# ppg_array_wireless.net
KiCad netlist of a schematic drawn in EAGLE
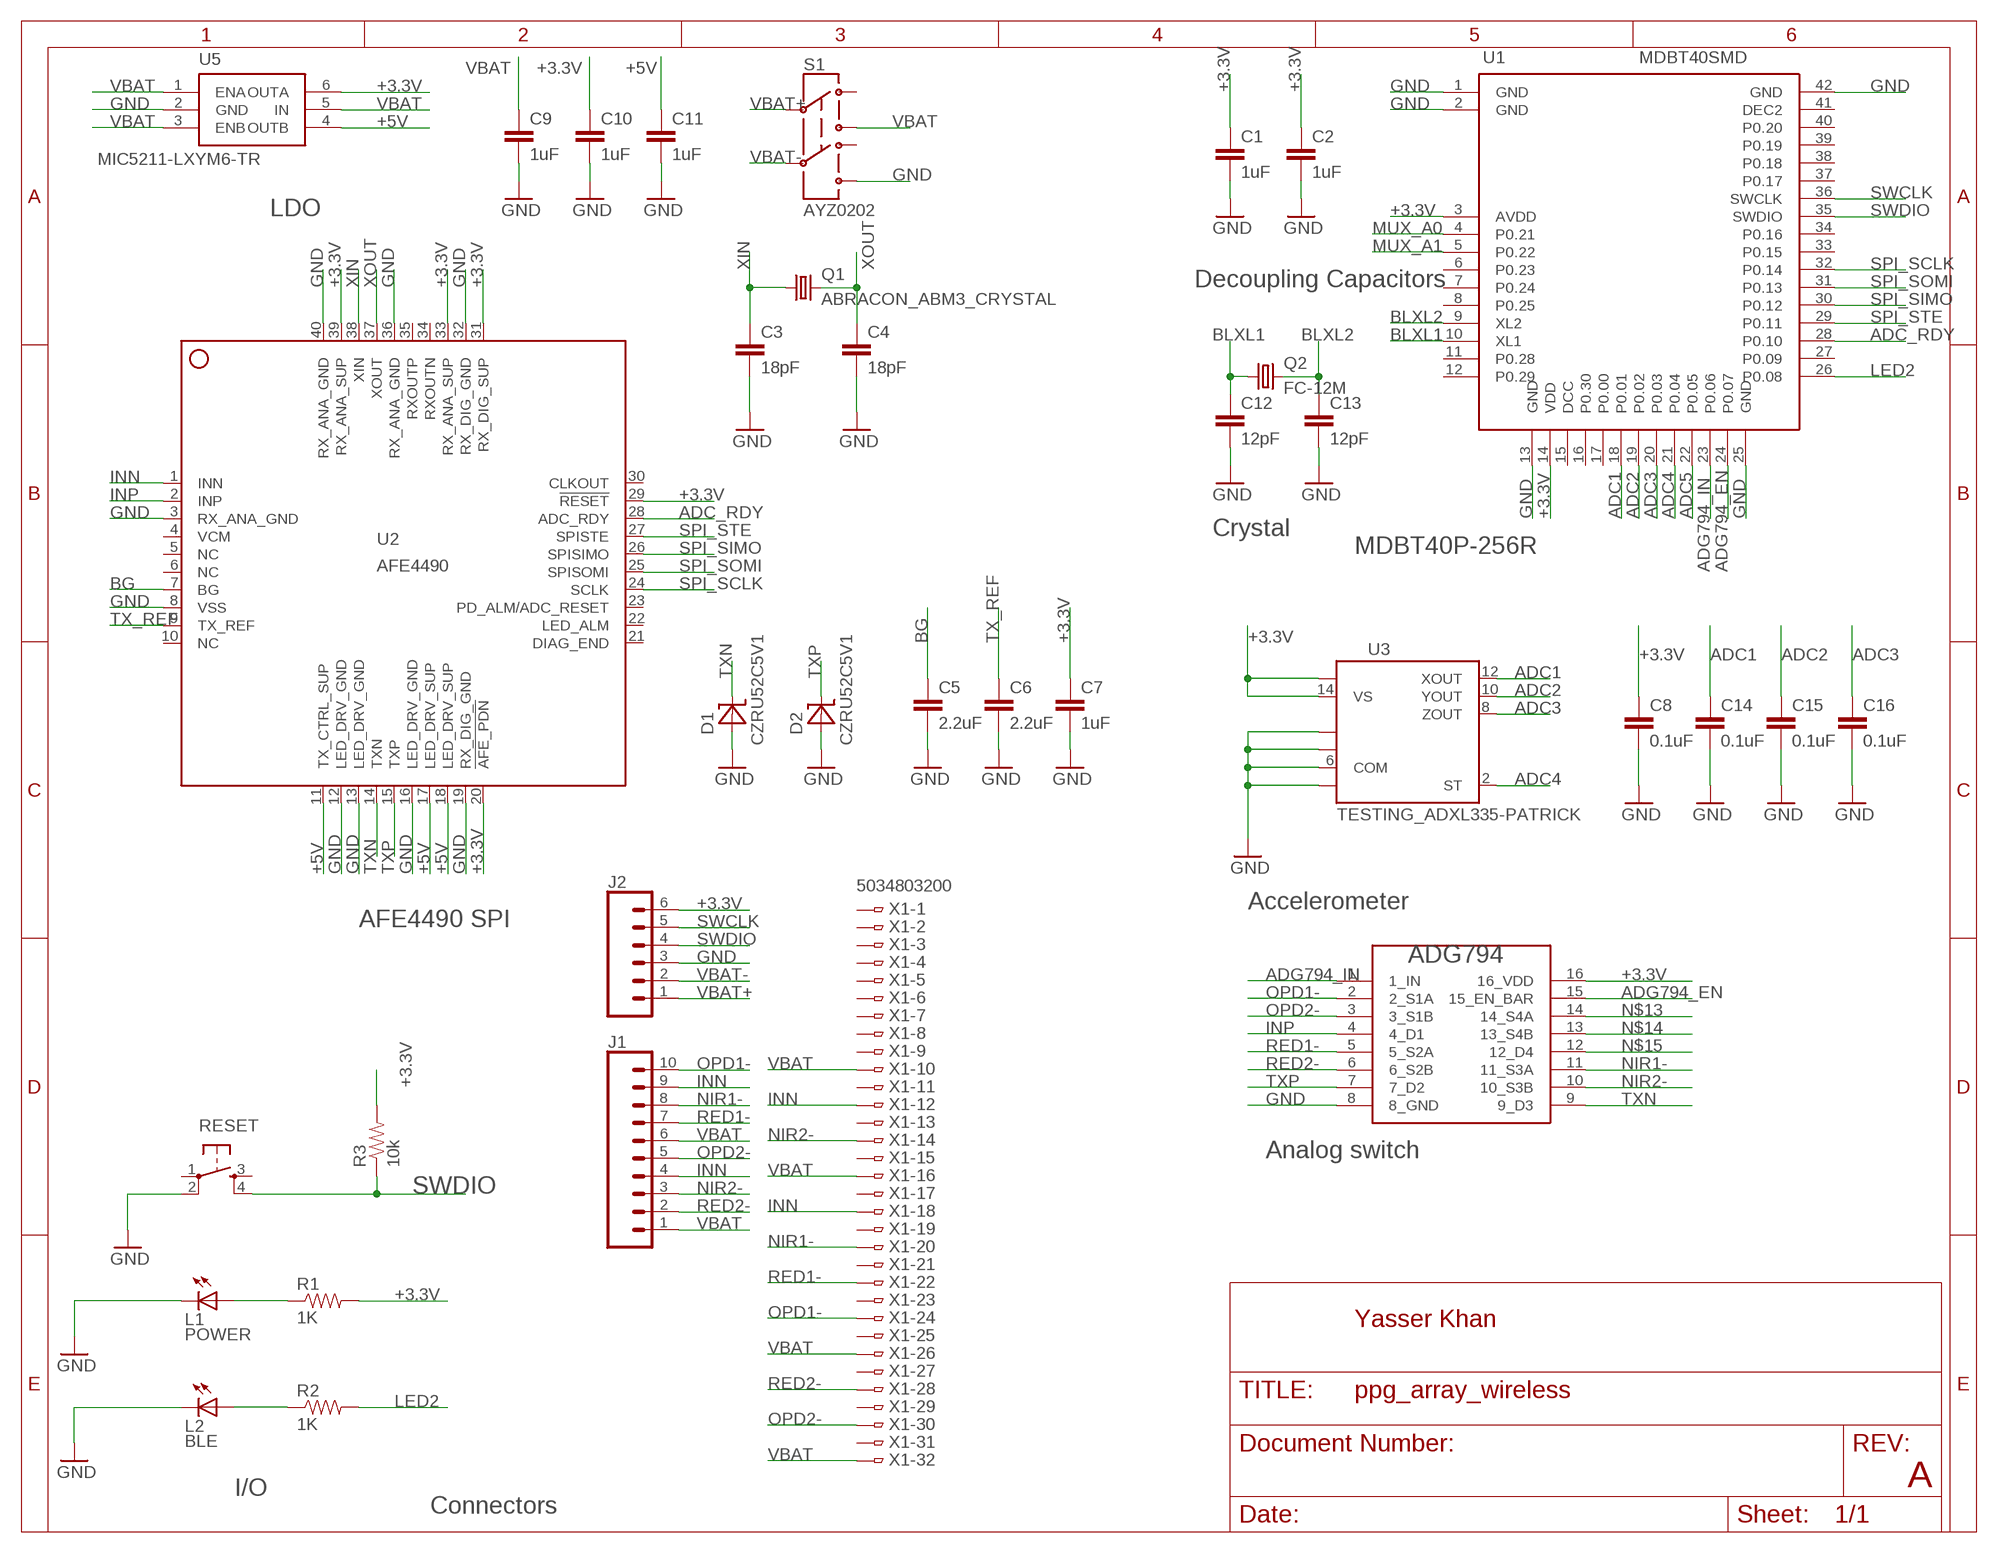
[diagram p0: schematic, sheet 1]

(export (version "E")
  (design (tool "Eeschema 10.0.6"))
  (components
    (comp (ref "C1")
      (value "1uF")
      (footprint "eagle-import:0603-CAP")
      (libsource (lib "eagle-import") (part "CAP0603-CAP"))
    )
    (comp (ref "C2")
      (value "1uF")
      (footprint "eagle-import:0603-CAP")
      (libsource (lib "eagle-import") (part "CAP0603-CAP"))
    )
    (comp (ref "C3")
      (value "18pF")
      (footprint "eagle-import:0603-CAP")
      (libsource (lib "eagle-import") (part "CAP0603-CAP"))
    )
    (comp (ref "C4")
      (value "18pF")
      (footprint "eagle-import:0603-CAP")
      (libsource (lib "eagle-import") (part "CAP0603-CAP"))
    )
    (comp (ref "C5")
      (value "2.2uF")
      (footprint "eagle-import:0603-CAP")
      (libsource (lib "eagle-import") (part "CAP0603-CAP"))
    )
    (comp (ref "C6")
      (value "2.2uF")
      (footprint "eagle-import:0603-CAP")
      (libsource (lib "eagle-import") (part "CAP0603-CAP"))
    )
    (comp (ref "C7")
      (value "1uF")
      (footprint "eagle-import:0603-CAP")
      (libsource (lib "eagle-import") (part "CAP0603-CAP"))
    )
    (comp (ref "C8")
      (value "0.1uF")
      (footprint "eagle-import:0603-CAP")
      (libsource (lib "eagle-import") (part "CAP0603-CAP"))
    )
    (comp (ref "C9")
      (value "1uF")
      (footprint "eagle-import:0603-CAP")
      (libsource (lib "eagle-import") (part "CAP0603-CAP"))
    )
    (comp (ref "C10")
      (value "1uF")
      (footprint "eagle-import:0603-CAP")
      (libsource (lib "eagle-import") (part "CAP0603-CAP"))
    )
    (comp (ref "C11")
      (value "1uF")
      (footprint "eagle-import:0603-CAP")
      (libsource (lib "eagle-import") (part "CAP0603-CAP"))
    )
    (comp (ref "C12")
      (value "12pF")
      (footprint "eagle-import:0603-CAP")
      (libsource (lib "eagle-import") (part "CAP0603-CAP"))
    )
    (comp (ref "C13")
      (value "12pF")
      (footprint "eagle-import:0603-CAP")
      (libsource (lib "eagle-import") (part "CAP0603-CAP"))
    )
    (comp (ref "C14")
      (value "0.1uF")
      (footprint "eagle-import:0603-CAP")
      (libsource (lib "eagle-import") (part "CAP0603-CAP"))
    )
    (comp (ref "C15")
      (value "0.1uF")
      (footprint "eagle-import:0603-CAP")
      (libsource (lib "eagle-import") (part "CAP0603-CAP"))
    )
    (comp (ref "C16")
      (value "0.1uF")
      (footprint "eagle-import:0603-CAP")
      (libsource (lib "eagle-import") (part "CAP0603-CAP"))
    )
    (comp (ref "D1")
      (value "CZRU52C5V1")
      (footprint "eagle-import:CZRU52C5V1")
      (libsource (lib "eagle-import") (part "CZRU52C5V1"))
    )
    (comp (ref "D2")
      (value "CZRU52C5V1")
      (footprint "eagle-import:CZRU52C5V1")
      (libsource (lib "eagle-import") (part "CZRU52C5V1"))
    )
    (comp (ref "J1")
      (value "CONN_10\"")
      (footprint "eagle-import:1X10")
      (libsource (lib "eagle-import") (part "CONN_10{dblquote}"))
    )
    (comp (ref "J2")
      (value "CONN_06SILK_FEMALE_PTH")
      (footprint "eagle-import:1X06")
      (libsource (lib "eagle-import") (part "CONN_06SILK_FEMALE_PTH"))
    )
    (comp (ref "L1")
      (value "POWER")
      (footprint "eagle-import:CHIP-LED0603")
      (libsource (lib "eagle-import") (part "LEDCHIP-LED0603"))
    )
    (comp (ref "L2")
      (value "BLE")
      (footprint "eagle-import:CHIP-LED0603")
      (libsource (lib "eagle-import") (part "LEDCHIP-LED0603"))
    )
    (comp (ref "Q1")
      (value "ABRACON_ABM3_CRYSTAL")
      (footprint "eagle-import:ABRACON_ABM3_CRYSTAL")
      (libsource (lib "eagle-import") (part "ABRACON_ABM3_CRYSTAL"))
    )
    (comp (ref "Q2")
      (value "FC-12M")
      (footprint "eagle-import:FC-12M")
      (libsource (lib "eagle-import") (part "FC-12M"))
    )
    (comp (ref "R1")
      (value "1K")
      (footprint "eagle-import:0603-RES")
      (libsource (lib "eagle-import") (part "RESISTOR0603-RES"))
    )
    (comp (ref "R2")
      (value "1K")
      (footprint "eagle-import:0603-RES")
      (libsource (lib "eagle-import") (part "RESISTOR0603-RES"))
    )
    (comp (ref "R3")
      (value "10k")
      (footprint "eagle-import:0603-RES")
      (libsource (lib "eagle-import") (part "RESISTOR0603-RES"))
    )
    (comp (ref "RESET")
      (value "TAC_SWITCHSMD")
      (footprint "eagle-import:TACTILE_SWITCH_SMD")
      (libsource (lib "eagle-import") (part "TAC_SWITCHSMD"))
    )
    (comp (ref "S1")
      (value "AYZ0202")
      (footprint "eagle-import:AYZ0202")
      (libsource (lib "eagle-import") (part "AYZ0202"))
    )
    (comp (ref "U1")
      (value "MDBT40SMD")
      (footprint "eagle-import:MDBT40")
      (libsource (lib "eagle-import") (part "MDBT40SMD"))
    )
    (comp (ref "U2")
      (value "AFE4490")
      (footprint "eagle-import:QFN40-6X6")
      (libsource (lib "eagle-import") (part "AFE4490"))
    )
    (comp (ref "U3")
      (value "TESTING_ADXL335-PATRICK")
      (footprint "eagle-import:TESTING_LFCSP-16")
      (libsource (lib "eagle-import") (part "TESTING_ADXL335-PATRICK"))
    )
    (comp (ref "U4")
      (value "ADG794")
      (footprint "eagle-import:QSOP16")
      (libsource (lib "eagle-import") (part "ADG794"))
    )
    (comp (ref "U5")
      (value "MIC5211-LXYM6-TR")
      (footprint "eagle-import:SOT-23-6")
      (libsource (lib "eagle-import") (part "MIC5211-LXYM6-TR"))
    )
    (comp (ref "X1")
      (value "5034803200")
      (footprint "eagle-import:5034803200")
      (libsource (lib "eagle-import") (part "5034803200"))
    )
  )
  (nets
    (net (code "1") (name "/+3.3V") (class "Default")
      (node (ref "C1") (pin "1") (pinfunction "1_1") (pintype "passive"))
      (node (ref "C10") (pin "1") (pinfunction "1_1") (pintype "passive"))
      (node (ref "C2") (pin "1") (pinfunction "1_1") (pintype "passive"))
      (node (ref "C7") (pin "1") (pinfunction "1_1") (pintype "passive"))
      (node (ref "C8") (pin "1") (pinfunction "1_1") (pintype "passive"))
      (node (ref "J2") (pin "6") (pinfunction "6_6") (pintype "passive"))
      (node (ref "R1") (pin "2") (pinfunction "2_2") (pintype "passive"))
      (node (ref "R3") (pin "2") (pinfunction "2_2") (pintype "passive"))
      (node (ref "U1") (pin "14") (pinfunction "VDD_14") (pintype "bidirectional"))
      (node (ref "U1") (pin "3") (pinfunction "AVDD_3") (pintype "bidirectional"))
      (node (ref "U2") (pin "20") (pinfunction "~{AFE_PDN}_20") (pintype "input"))
      (node (ref "U2") (pin "29") (pinfunction "~{RESET}_29") (pintype "input"))
      (node (ref "U2") (pin "31") (pinfunction "RX_DIG_SUP_31") (pintype "power_in"))
      (node (ref "U2") (pin "33") (pinfunction "RX_ANA_SUP_33") (pintype "power_in"))
      (node (ref "U2") (pin "39") (pinfunction "RX_ANA_SUP_39") (pintype "power_in"))
      (node (ref "U3") (pin "14") (pinfunction "VS_14") (pintype "bidirectional"))
      (node (ref "U3") (pin "15") (pinfunction "VS_15") (pintype "bidirectional"))
      (node (ref "U4") (pin "16") (pinfunction "16_VDD_16") (pintype "bidirectional"))
      (node (ref "U5") (pin "6") (pinfunction "OUTA_6") (pintype "bidirectional"))
    )
    (net (code "2") (name "/+5V") (class "Default")
      (node (ref "C11") (pin "1") (pinfunction "1_1") (pintype "passive"))
      (node (ref "U2") (pin "11") (pinfunction "TX_CTRL_SUP_11") (pintype "power_in"))
      (node (ref "U2") (pin "17") (pinfunction "LED_DRV_SUP_17") (pintype "power_in"))
      (node (ref "U2") (pin "18") (pinfunction "LED_DRV_SUP_18") (pintype "power_in"))
      (node (ref "U5") (pin "4") (pinfunction "OUTB_4") (pintype "bidirectional"))
    )
    (net (code "3") (name "/ADC1") (class "Default")
      (node (ref "C14") (pin "1") (pinfunction "1_1") (pintype "passive"))
      (node (ref "U1") (pin "18") (pinfunction "P0.01_18") (pintype "bidirectional"))
      (node (ref "U3") (pin "12") (pinfunction "XOUT_12") (pintype "bidirectional"))
    )
    (net (code "4") (name "/ADC2") (class "Default")
      (node (ref "C15") (pin "1") (pinfunction "1_1") (pintype "passive"))
      (node (ref "U1") (pin "19") (pinfunction "P0.02_19") (pintype "bidirectional"))
      (node (ref "U3") (pin "10") (pinfunction "YOUT_10") (pintype "bidirectional"))
    )
    (net (code "5") (name "/ADC3") (class "Default")
      (node (ref "C16") (pin "1") (pinfunction "1_1") (pintype "passive"))
      (node (ref "U1") (pin "20") (pinfunction "P0.03_20") (pintype "bidirectional"))
      (node (ref "U3") (pin "8") (pinfunction "ZOUT_8") (pintype "bidirectional"))
    )
    (net (code "6") (name "/ADC4") (class "Default")
      (node (ref "U1") (pin "21") (pinfunction "P0.04_21") (pintype "bidirectional"))
      (node (ref "U3") (pin "2") (pinfunction "ST_2") (pintype "bidirectional"))
    )
    (net (code "7") (name "/ADC5") (class "Default")
      (node (ref "U1") (pin "22") (pinfunction "P0.05_22") (pintype "bidirectional"))
    )
    (net (code "8") (name "/ADC_RDY") (class "Default")
      (node (ref "U1") (pin "28") (pinfunction "P0.10_28") (pintype "bidirectional"))
      (node (ref "U2") (pin "28") (pinfunction "ADC_RDY_28") (pintype "output"))
    )
    (net (code "9") (name "/ADG794_EN") (class "Default")
      (node (ref "U1") (pin "24") (pinfunction "P0.07_24") (pintype "bidirectional"))
      (node (ref "U4") (pin "15") (pinfunction "15_EN_BAR_15") (pintype "bidirectional"))
    )
    (net (code "10") (name "/ADG794_IN") (class "Default")
      (node (ref "U1") (pin "23") (pinfunction "P0.06_23") (pintype "bidirectional"))
      (node (ref "U4") (pin "1") (pinfunction "1_IN_1") (pintype "bidirectional"))
    )
    (net (code "11") (name "/BG") (class "Default")
      (node (ref "C5") (pin "1") (pinfunction "1_1") (pintype "passive"))
      (node (ref "U2") (pin "7") (pinfunction "BG_7") (pintype "passive"))
    )
    (net (code "12") (name "/BLXL1") (class "Default")
      (node (ref "C12") (pin "1") (pinfunction "1_1") (pintype "passive"))
      (node (ref "Q2") (pin "1") (pinfunction "1_1") (pintype "passive"))
      (node (ref "U1") (pin "10") (pinfunction "XL1_10") (pintype "bidirectional"))
    )
    (net (code "13") (name "/BLXL2") (class "Default")
      (node (ref "C13") (pin "1") (pinfunction "1_1") (pintype "passive"))
      (node (ref "Q2") (pin "2") (pinfunction "2_2") (pintype "passive"))
      (node (ref "U1") (pin "9") (pinfunction "XL2_9") (pintype "bidirectional"))
    )
    (net (code "14") (name "/INN") (class "Default")
      (node (ref "J1") (pin "4") (pinfunction "4_4") (pintype "passive"))
      (node (ref "J1") (pin "9") (pinfunction "9_9") (pintype "passive"))
      (node (ref "U2") (pin "1") (pinfunction "INN_1") (pintype "input"))
      (node (ref "X1") (pin "12") (pinfunction "1_12") (pintype "passive"))
      (node (ref "X1") (pin "18") (pinfunction "1_18") (pintype "passive"))
    )
    (net (code "15") (name "/INP") (class "Default")
      (node (ref "U2") (pin "2") (pinfunction "INP_2") (pintype "input"))
      (node (ref "U4") (pin "4") (pinfunction "4_D1_4") (pintype "bidirectional"))
    )
    (net (code "16") (name "/LED2") (class "Default")
      (node (ref "R2") (pin "2") (pinfunction "2_2") (pintype "passive"))
      (node (ref "U1") (pin "26") (pinfunction "P0.08_26") (pintype "bidirectional"))
    )
    (net (code "17") (name "/MUX_A0") (class "Default")
      (node (ref "U1") (pin "4") (pinfunction "P0.21_4") (pintype "bidirectional"))
    )
    (net (code "18") (name "/MUX_A1") (class "Default")
      (node (ref "U1") (pin "5") (pinfunction "P0.22_5") (pintype "bidirectional"))
    )
    (net (code "19") (name "/N$13") (class "Default")
      (node (ref "U4") (pin "14") (pinfunction "14_S4A_14") (pintype "bidirectional"))
    )
    (net (code "20") (name "/N$14") (class "Default")
      (node (ref "U4") (pin "13") (pinfunction "13_S4B_13") (pintype "bidirectional"))
    )
    (net (code "21") (name "/N$15") (class "Default")
      (node (ref "U4") (pin "12") (pinfunction "12_D4_12") (pintype "bidirectional"))
    )
    (net (code "22") (name "/NIR1-") (class "Default")
      (node (ref "J1") (pin "8") (pinfunction "8_8") (pintype "passive"))
      (node (ref "U4") (pin "11") (pinfunction "11_S3A_11") (pintype "bidirectional"))
      (node (ref "X1") (pin "20") (pinfunction "1_20") (pintype "passive"))
    )
    (net (code "23") (name "/NIR2-") (class "Default")
      (node (ref "J1") (pin "3") (pinfunction "3_3") (pintype "passive"))
      (node (ref "U4") (pin "10") (pinfunction "10_S3B_10") (pintype "bidirectional"))
      (node (ref "X1") (pin "14") (pinfunction "1_14") (pintype "passive"))
    )
    (net (code "24") (name "/OPD1-") (class "Default")
      (node (ref "J1") (pin "10") (pinfunction "10_10") (pintype "passive"))
      (node (ref "U4") (pin "2") (pinfunction "2_S1A_2") (pintype "bidirectional"))
      (node (ref "X1") (pin "24") (pinfunction "1_24") (pintype "passive"))
    )
    (net (code "25") (name "/OPD2-") (class "Default")
      (node (ref "J1") (pin "5") (pinfunction "5_5") (pintype "passive"))
      (node (ref "U4") (pin "3") (pinfunction "3_S1B_3") (pintype "bidirectional"))
      (node (ref "X1") (pin "30") (pinfunction "1_30") (pintype "passive"))
    )
    (net (code "26") (name "/RED1-") (class "Default")
      (node (ref "J1") (pin "7") (pinfunction "7_7") (pintype "passive"))
      (node (ref "U4") (pin "5") (pinfunction "5_S2A_5") (pintype "bidirectional"))
      (node (ref "X1") (pin "22") (pinfunction "1_22") (pintype "passive"))
    )
    (net (code "27") (name "/RED2-") (class "Default")
      (node (ref "J1") (pin "2") (pinfunction "2_2") (pintype "passive"))
      (node (ref "U4") (pin "6") (pinfunction "6_S2B_6") (pintype "bidirectional"))
      (node (ref "X1") (pin "28") (pinfunction "1_28") (pintype "passive"))
    )
    (net (code "28") (name "/SPI_SCLK") (class "Default")
      (node (ref "U1") (pin "32") (pinfunction "P0.14_32") (pintype "bidirectional"))
      (node (ref "U2") (pin "24") (pinfunction "SCLK_24") (pintype "input"))
    )
    (net (code "29") (name "/SPI_SIMO") (class "Default")
      (node (ref "U1") (pin "30") (pinfunction "P0.12_30") (pintype "bidirectional"))
      (node (ref "U2") (pin "26") (pinfunction "SPISIMO_26") (pintype "input"))
    )
    (net (code "30") (name "/SPI_SOMI") (class "Default")
      (node (ref "U1") (pin "31") (pinfunction "P0.13_31") (pintype "bidirectional"))
      (node (ref "U2") (pin "25") (pinfunction "SPISOMI_25") (pintype "output"))
    )
    (net (code "31") (name "/SPI_STE") (class "Default")
      (node (ref "U1") (pin "29") (pinfunction "P0.11_29") (pintype "bidirectional"))
      (node (ref "U2") (pin "27") (pinfunction "SPISTE_27") (pintype "input"))
    )
    (net (code "32") (name "/SWCLK") (class "Default")
      (node (ref "J2") (pin "5") (pinfunction "5_5") (pintype "passive"))
      (node (ref "U1") (pin "36") (pinfunction "SWCLK_36") (pintype "bidirectional"))
    )
    (net (code "33") (name "/SWDIO") (class "Default")
      (node (ref "J2") (pin "4") (pinfunction "4_4") (pintype "passive"))
      (node (ref "R3") (pin "1") (pinfunction "1_1") (pintype "passive"))
      (node (ref "RESET") (pin "4") (pinfunction "4_4") (pintype "passive"))
      (node (ref "U1") (pin "35") (pinfunction "SWDIO_35") (pintype "bidirectional"))
    )
    (net (code "34") (name "/TXN") (class "Default")
      (node (ref "D1") (pin "C") (pinfunction "C_C") (pintype "passive"))
      (node (ref "U2") (pin "14") (pinfunction "TXN_14") (pintype "output"))
      (node (ref "U4") (pin "9") (pinfunction "9_D3_9") (pintype "bidirectional"))
    )
    (net (code "35") (name "/TXP") (class "Default")
      (node (ref "D2") (pin "C") (pinfunction "C_C") (pintype "passive"))
      (node (ref "U2") (pin "15") (pinfunction "TXP_15") (pintype "output"))
      (node (ref "U4") (pin "7") (pinfunction "7_D2_7") (pintype "bidirectional"))
    )
    (net (code "36") (name "/TX_REF") (class "Default")
      (node (ref "C6") (pin "1") (pinfunction "1_1") (pintype "passive"))
      (node (ref "U2") (pin "9") (pinfunction "TX_REF_9") (pintype "output"))
    )
    (net (code "37") (name "/VBAT") (class "Default")
      (node (ref "C9") (pin "1") (pinfunction "1_1") (pintype "passive"))
      (node (ref "J1") (pin "1") (pinfunction "1_1") (pintype "passive"))
      (node (ref "J1") (pin "6") (pinfunction "6_6") (pintype "passive"))
      (node (ref "S1") (pin "1") (pinfunction "3_1") (pintype "bidirectional"))
      (node (ref "U5") (pin "1") (pinfunction "ENA_1") (pintype "bidirectional"))
      (node (ref "U5") (pin "3") (pinfunction "ENB_3") (pintype "bidirectional"))
      (node (ref "U5") (pin "5") (pinfunction "IN_5") (pintype "bidirectional"))
      (node (ref "X1") (pin "10") (pinfunction "1_10") (pintype "passive"))
      (node (ref "X1") (pin "16") (pinfunction "1_16") (pintype "passive"))
      (node (ref "X1") (pin "26") (pinfunction "1_26") (pintype "passive"))
      (node (ref "X1") (pin "32") (pinfunction "1_32") (pintype "passive"))
    )
    (net (code "38") (name "/VBAT+") (class "Default")
      (node (ref "J2") (pin "1") (pinfunction "1_1") (pintype "passive"))
      (node (ref "S1") (pin "2") (pinfunction "2_2") (pintype "bidirectional"))
    )
    (net (code "39") (name "/VBAT-") (class "Default")
      (node (ref "J2") (pin "2") (pinfunction "2_2") (pintype "passive"))
      (node (ref "S1") (pin "5") (pinfunction "5_5") (pintype "bidirectional"))
    )
    (net (code "40") (name "/XIN") (class "Default")
      (node (ref "C3") (pin "1") (pinfunction "1_1") (pintype "passive"))
      (node (ref "Q1") (pin "P$1") (pinfunction "1_P$1") (pintype "passive"))
      (node (ref "U2") (pin "38") (pinfunction "XIN_38") (pintype "input"))
    )
    (net (code "41") (name "/XOUT") (class "Default")
      (node (ref "C4") (pin "1") (pinfunction "1_1") (pintype "passive"))
      (node (ref "Q1") (pin "P$2") (pinfunction "2_P$2") (pintype "passive"))
      (node (ref "U2") (pin "37") (pinfunction "XOUT_37") (pintype "output"))
    )
    (net (code "42") (name "GND") (class "Default")
      (node (ref "C1") (pin "2") (pinfunction "2_2") (pintype "passive"))
      (node (ref "C10") (pin "2") (pinfunction "2_2") (pintype "passive"))
      (node (ref "C11") (pin "2") (pinfunction "2_2") (pintype "passive"))
      (node (ref "C12") (pin "2") (pinfunction "2_2") (pintype "passive"))
      (node (ref "C13") (pin "2") (pinfunction "2_2") (pintype "passive"))
      (node (ref "C14") (pin "2") (pinfunction "2_2") (pintype "passive"))
      (node (ref "C15") (pin "2") (pinfunction "2_2") (pintype "passive"))
      (node (ref "C16") (pin "2") (pinfunction "2_2") (pintype "passive"))
      (node (ref "C2") (pin "2") (pinfunction "2_2") (pintype "passive"))
      (node (ref "C3") (pin "2") (pinfunction "2_2") (pintype "passive"))
      (node (ref "C4") (pin "2") (pinfunction "2_2") (pintype "passive"))
      (node (ref "C5") (pin "2") (pinfunction "2_2") (pintype "passive"))
      (node (ref "C6") (pin "2") (pinfunction "2_2") (pintype "passive"))
      (node (ref "C7") (pin "2") (pinfunction "2_2") (pintype "passive"))
      (node (ref "C8") (pin "2") (pinfunction "2_2") (pintype "passive"))
      (node (ref "C9") (pin "2") (pinfunction "2_2") (pintype "passive"))
      (node (ref "D1") (pin "A") (pinfunction "A_A") (pintype "passive"))
      (node (ref "D2") (pin "A") (pinfunction "A_A") (pintype "passive"))
      (node (ref "J2") (pin "3") (pinfunction "3_3") (pintype "passive"))
      (node (ref "L1") (pin "C") (pinfunction "C_C") (pintype "passive"))
      (node (ref "L2") (pin "C") (pinfunction "C_C") (pintype "passive"))
      (node (ref "RESET") (pin "2") (pinfunction "2_2") (pintype "passive"))
      (node (ref "S1") (pin "4") (pinfunction "6_4") (pintype "bidirectional"))
      (node (ref "U1") (pin "1") (pinfunction "GND_1") (pintype "bidirectional"))
      (node (ref "U1") (pin "13") (pinfunction "GND_13") (pintype "bidirectional"))
      (node (ref "U1") (pin "2") (pinfunction "GND_2") (pintype "bidirectional"))
      (node (ref "U1") (pin "25") (pinfunction "GND_25") (pintype "bidirectional"))
      (node (ref "U1") (pin "42") (pinfunction "GND_42") (pintype "bidirectional"))
      (node (ref "U2") (pin "12") (pinfunction "LED_DRV_GND_12") (pintype "power_in"))
      (node (ref "U2") (pin "13") (pinfunction "LED_DRV_GND_13") (pintype "power_in"))
      (node (ref "U2") (pin "16") (pinfunction "LED_DRV_GND_16") (pintype "power_in"))
      (node (ref "U2") (pin "19") (pinfunction "RX_DIG_GND_19") (pintype "power_in"))
      (node (ref "U2") (pin "3") (pinfunction "RX_ANA_GND_3") (pintype "power_in"))
      (node (ref "U2") (pin "32") (pinfunction "RX_DIG_GND_32") (pintype "power_in"))
      (node (ref "U2") (pin "36") (pinfunction "RX_ANA_GND_36") (pintype "power_in"))
      (node (ref "U2") (pin "40") (pinfunction "RX_ANA_GND_40") (pintype "power_in"))
      (node (ref "U2") (pin "8") (pinfunction "VSS_8") (pintype "power_in"))
      (node (ref "U3") (pin "3") (pinfunction "COM_3") (pintype "bidirectional"))
      (node (ref "U3") (pin "5") (pinfunction "COM_5") (pintype "bidirectional"))
      (node (ref "U3") (pin "6") (pinfunction "COM_6") (pintype "bidirectional"))
      (node (ref "U3") (pin "7") (pinfunction "COM_7") (pintype "bidirectional"))
      (node (ref "U4") (pin "8") (pinfunction "8_GND_8") (pintype "bidirectional"))
      (node (ref "U5") (pin "2") (pinfunction "GND_2") (pintype "bidirectional"))
    )
    (net (code "43") (name "Net-(L1-PadA)") (class "Default")
      (node (ref "L1") (pin "A") (pinfunction "A_A") (pintype "passive"))
      (node (ref "R1") (pin "1") (pinfunction "1_1") (pintype "passive"))
    )
    (net (code "44") (name "Net-(L2-PadA)") (class "Default")
      (node (ref "L2") (pin "A") (pinfunction "A_A") (pintype "passive"))
      (node (ref "R2") (pin "1") (pinfunction "1_1") (pintype "passive"))
    )
    (net (code "45") (name "unconnected-(RESET-Pad1)") (class "Default")
      (node (ref "RESET") (pin "1") (pinfunction "1_1") (pintype "passive"))
    )
    (net (code "46") (name "unconnected-(RESET-Pad3)") (class "Default")
      (node (ref "RESET") (pin "3") (pinfunction "3_3") (pintype "passive"))
    )
    (net (code "47") (name "unconnected-(S1-1-Pad3)") (class "Default")
      (node (ref "S1") (pin "3") (pinfunction "1_3") (pintype "bidirectional"))
    )
    (net (code "48") (name "unconnected-(S1-4-Pad6)") (class "Default")
      (node (ref "S1") (pin "6") (pinfunction "4_6") (pintype "bidirectional"))
    )
    (net (code "49") (name "unconnected-(U1-DCC-Pad15)") (class "Default")
      (node (ref "U1") (pin "15") (pinfunction "DCC_15") (pintype "bidirectional"))
    )
    (net (code "50") (name "unconnected-(U1-DEC2-Pad41)") (class "Default")
      (node (ref "U1") (pin "41") (pinfunction "DEC2_41") (pintype "bidirectional"))
    )
    (net (code "51") (name "unconnected-(U1-P0.00-Pad17)") (class "Default")
      (node (ref "U1") (pin "17") (pinfunction "P0.00_17") (pintype "bidirectional"))
    )
    (net (code "52") (name "unconnected-(U1-P0.09-Pad27)") (class "Default")
      (node (ref "U1") (pin "27") (pinfunction "P0.09_27") (pintype "bidirectional"))
    )
    (net (code "53") (name "unconnected-(U1-P0.15-Pad33)") (class "Default")
      (node (ref "U1") (pin "33") (pinfunction "P0.15_33") (pintype "bidirectional"))
    )
    (net (code "54") (name "unconnected-(U1-P0.16-Pad34)") (class "Default")
      (node (ref "U1") (pin "34") (pinfunction "P0.16_34") (pintype "bidirectional"))
    )
    (net (code "55") (name "unconnected-(U1-P0.17-Pad37)") (class "Default")
      (node (ref "U1") (pin "37") (pinfunction "P0.17_37") (pintype "bidirectional"))
    )
    (net (code "56") (name "unconnected-(U1-P0.18-Pad38)") (class "Default")
      (node (ref "U1") (pin "38") (pinfunction "P0.18_38") (pintype "bidirectional"))
    )
    (net (code "57") (name "unconnected-(U1-P0.19-Pad39)") (class "Default")
      (node (ref "U1") (pin "39") (pinfunction "P0.19_39") (pintype "bidirectional"))
    )
    (net (code "58") (name "unconnected-(U1-P0.20-Pad40)") (class "Default")
      (node (ref "U1") (pin "40") (pinfunction "P0.20_40") (pintype "bidirectional"))
    )
    (net (code "59") (name "unconnected-(U1-P0.23-Pad6)") (class "Default")
      (node (ref "U1") (pin "6") (pinfunction "P0.23_6") (pintype "bidirectional"))
    )
    (net (code "60") (name "unconnected-(U1-P0.24-Pad7)") (class "Default")
      (node (ref "U1") (pin "7") (pinfunction "P0.24_7") (pintype "bidirectional"))
    )
    (net (code "61") (name "unconnected-(U1-P0.25-Pad8)") (class "Default")
      (node (ref "U1") (pin "8") (pinfunction "P0.25_8") (pintype "bidirectional"))
    )
    (net (code "62") (name "unconnected-(U1-P0.28-Pad11)") (class "Default")
      (node (ref "U1") (pin "11") (pinfunction "P0.28_11") (pintype "bidirectional"))
    )
    (net (code "63") (name "unconnected-(U1-P0.29-Pad12)") (class "Default")
      (node (ref "U1") (pin "12") (pinfunction "P0.29_12") (pintype "bidirectional"))
    )
    (net (code "64") (name "unconnected-(U1-P0.30-Pad16)") (class "Default")
      (node (ref "U1") (pin "16") (pinfunction "P0.30_16") (pintype "bidirectional"))
    )
    (net (code "65") (name "unconnected-(U2A-CLKOUT-Pad30)") (class "Default")
      (node (ref "U2") (pin "30") (pinfunction "CLKOUT_30") (pintype "output"))
    )
    (net (code "66") (name "unconnected-(U2A-DIAG_END-Pad21)") (class "Default")
      (node (ref "U2") (pin "21") (pinfunction "DIAG_END_21") (pintype "output"))
    )
    (net (code "67") (name "unconnected-(U2A-LED_ALM-Pad22)") (class "Default")
      (node (ref "U2") (pin "22") (pinfunction "LED_ALM_22") (pintype "output"))
    )
    (net (code "68") (name "unconnected-(U2A-NC-Pad5)") (class "Default")
      (node (ref "U2") (pin "5") (pinfunction "NC_5") (pintype "no_connect"))
    )
    (net (code "69") (name "unconnected-(U2A-NC-Pad6)") (class "Default")
      (node (ref "U2") (pin "6") (pinfunction "NC_6") (pintype "no_connect"))
    )
    (net (code "70") (name "unconnected-(U2A-NC-Pad10)") (class "Default")
      (node (ref "U2") (pin "10") (pinfunction "NC_10") (pintype "no_connect"))
    )
    (net (code "71") (name "unconnected-(U2A-PD_ALM{slash}ADC_RESET-Pad23)") (class "Default")
      (node (ref "U2") (pin "23") (pinfunction "PD_ALM/ADC_RESET_23") (pintype "bidirectional"))
    )
    (net (code "72") (name "unconnected-(U2A-RXOUTN-Pad34)") (class "Default")
      (node (ref "U2") (pin "34") (pinfunction "RXOUTN_34") (pintype "output"))
    )
    (net (code "73") (name "unconnected-(U2A-RXOUTP-Pad35)") (class "Default")
      (node (ref "U2") (pin "35") (pinfunction "RXOUTP_35") (pintype "output"))
    )
    (net (code "74") (name "unconnected-(U2A-VCM-Pad4)") (class "Default")
      (node (ref "U2") (pin "4") (pinfunction "VCM_4") (pintype "output"))
    )
    (net (code "75") (name "unconnected-(X1-Pad1)") (class "Default")
      (node (ref "X1") (pin "1") (pinfunction "1_1") (pintype "passive"))
    )
    (net (code "76") (name "unconnected-(X1AA-1-Pad4)") (class "Default")
      (node (ref "X1") (pin "4") (pinfunction "1_4") (pintype "passive"))
    )
    (net (code "77") (name "unconnected-(X1AB-1-Pad5)") (class "Default")
      (node (ref "X1") (pin "5") (pinfunction "1_5") (pintype "passive"))
    )
    (net (code "78") (name "unconnected-(X1AC-1-Pad6)") (class "Default")
      (node (ref "X1") (pin "6") (pinfunction "1_6") (pintype "passive"))
    )
    (net (code "79") (name "unconnected-(X1AD-1-Pad7)") (class "Default")
      (node (ref "X1") (pin "7") (pinfunction "1_7") (pintype "passive"))
    )
    (net (code "80") (name "unconnected-(X1AE-1-Pad8)") (class "Default")
      (node (ref "X1") (pin "8") (pinfunction "1_8") (pintype "passive"))
    )
    (net (code "81") (name "unconnected-(X1AF-1-Pad9)") (class "Default")
      (node (ref "X1") (pin "9") (pinfunction "1_9") (pintype "passive"))
    )
    (net (code "82") (name "unconnected-(X1C-1-Pad11)") (class "Default")
      (node (ref "X1") (pin "11") (pinfunction "1_11") (pintype "passive"))
    )
    (net (code "83") (name "unconnected-(X1E-1-Pad13)") (class "Default")
      (node (ref "X1") (pin "13") (pinfunction "1_13") (pintype "passive"))
    )
    (net (code "84") (name "unconnected-(X1G-1-Pad15)") (class "Default")
      (node (ref "X1") (pin "15") (pinfunction "1_15") (pintype "passive"))
    )
    (net (code "85") (name "unconnected-(X1I-1-Pad17)") (class "Default")
      (node (ref "X1") (pin "17") (pinfunction "1_17") (pintype "passive"))
    )
    (net (code "86") (name "unconnected-(X1K-1-Pad19)") (class "Default")
      (node (ref "X1") (pin "19") (pinfunction "1_19") (pintype "passive"))
    )
    (net (code "87") (name "unconnected-(X1L-1-Pad2)") (class "Default")
      (node (ref "X1") (pin "2") (pinfunction "1_2") (pintype "passive"))
    )
    (net (code "88") (name "unconnected-(X1N-1-Pad21)") (class "Default")
      (node (ref "X1") (pin "21") (pinfunction "1_21") (pintype "passive"))
    )
    (net (code "89") (name "unconnected-(X1P-1-Pad23)") (class "Default")
      (node (ref "X1") (pin "23") (pinfunction "1_23") (pintype "passive"))
    )
    (net (code "90") (name "unconnected-(X1R-1-Pad25)") (class "Default")
      (node (ref "X1") (pin "25") (pinfunction "1_25") (pintype "passive"))
    )
    (net (code "91") (name "unconnected-(X1T-1-Pad27)") (class "Default")
      (node (ref "X1") (pin "27") (pinfunction "1_27") (pintype "passive"))
    )
    (net (code "92") (name "unconnected-(X1V-1-Pad29)") (class "Default")
      (node (ref "X1") (pin "29") (pinfunction "1_29") (pintype "passive"))
    )
    (net (code "93") (name "unconnected-(X1W-1-Pad3)") (class "Default")
      (node (ref "X1") (pin "3") (pinfunction "1_3") (pintype "passive"))
    )
    (net (code "94") (name "unconnected-(X1Y-1-Pad31)") (class "Default")
      (node (ref "X1") (pin "31") (pinfunction "1_31") (pintype "passive"))
    )
  )
)
